# contbrd.net
KiCad netlist of a schematic drawn in EAGLE
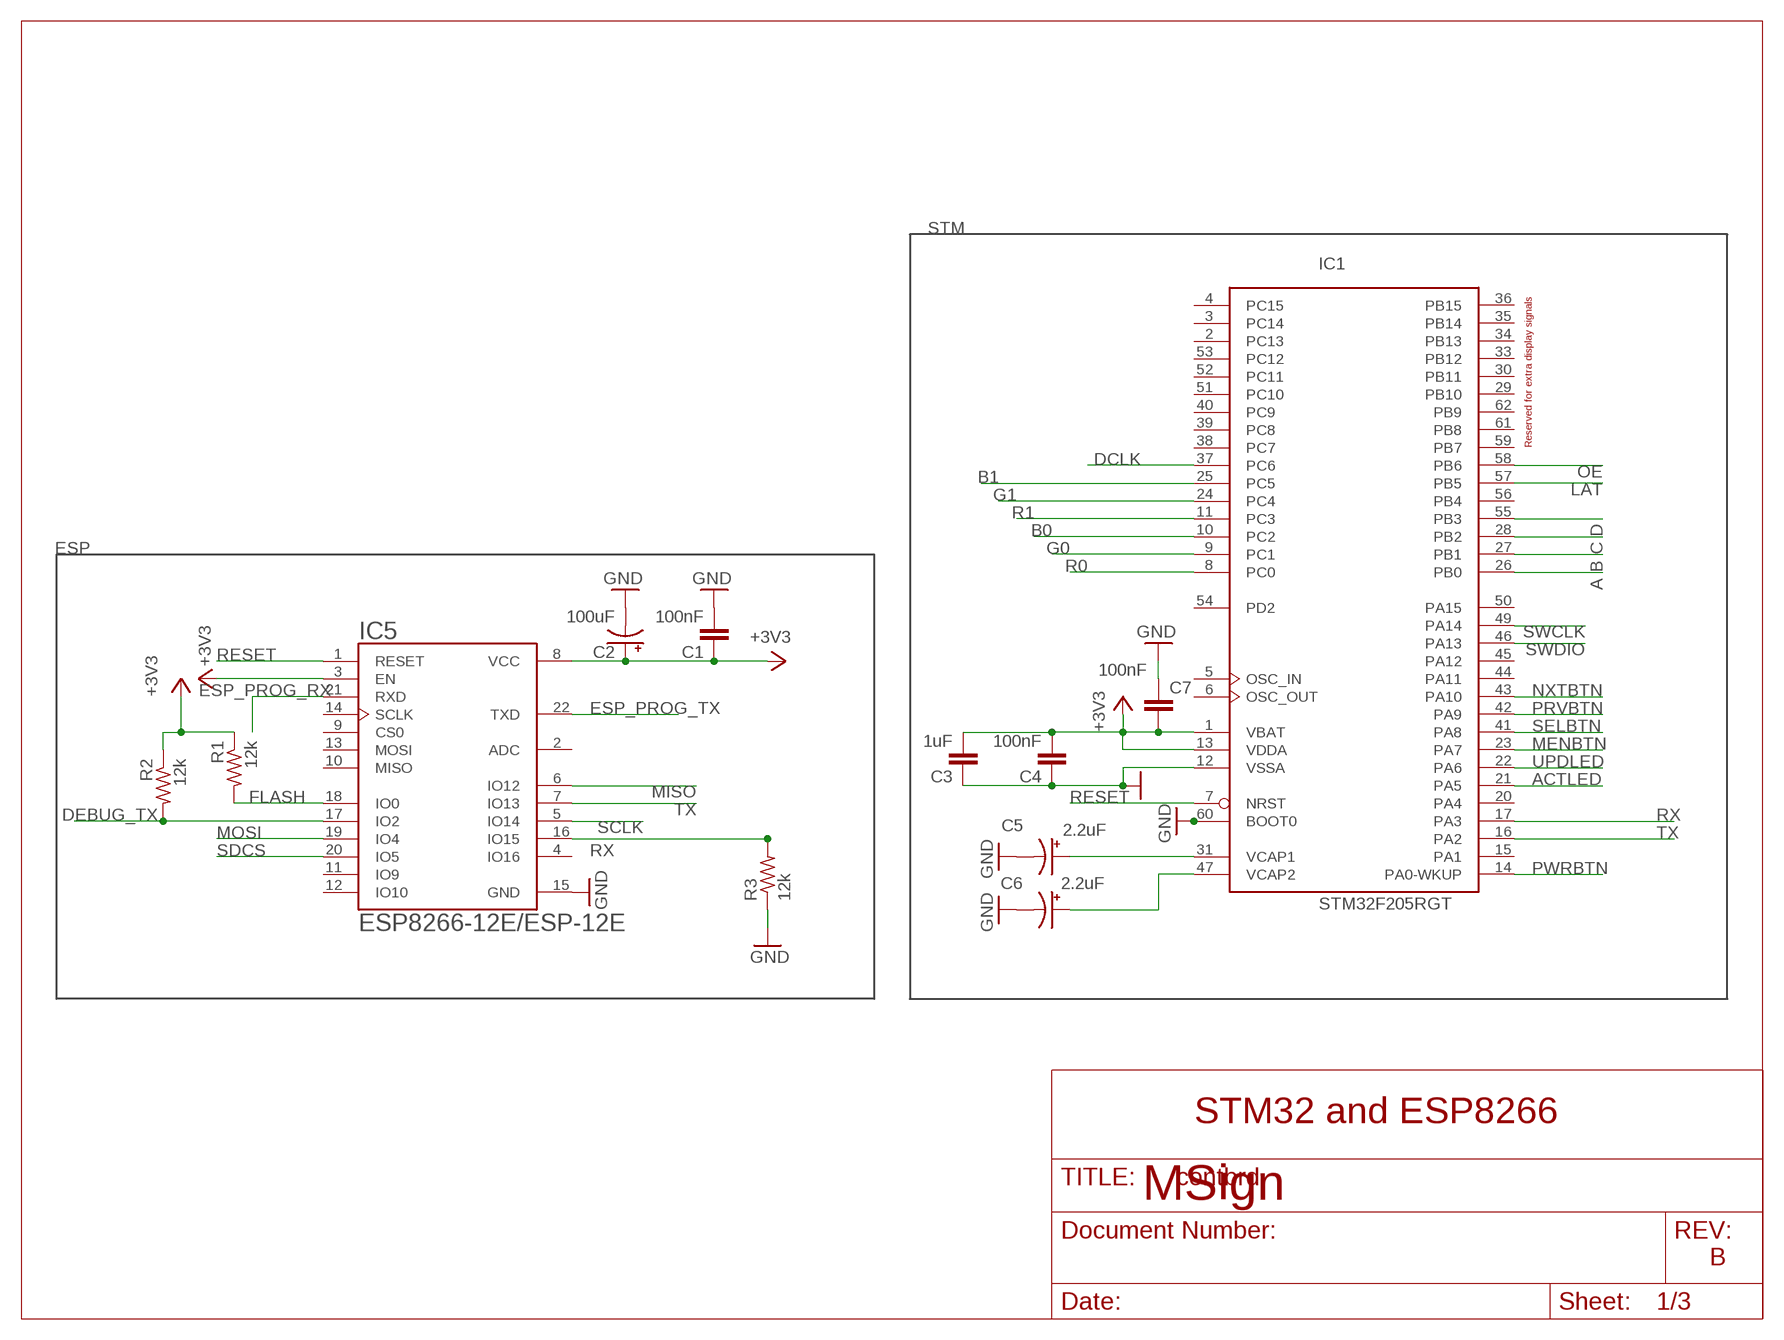
[diagram p0: schematic, sheet 1]
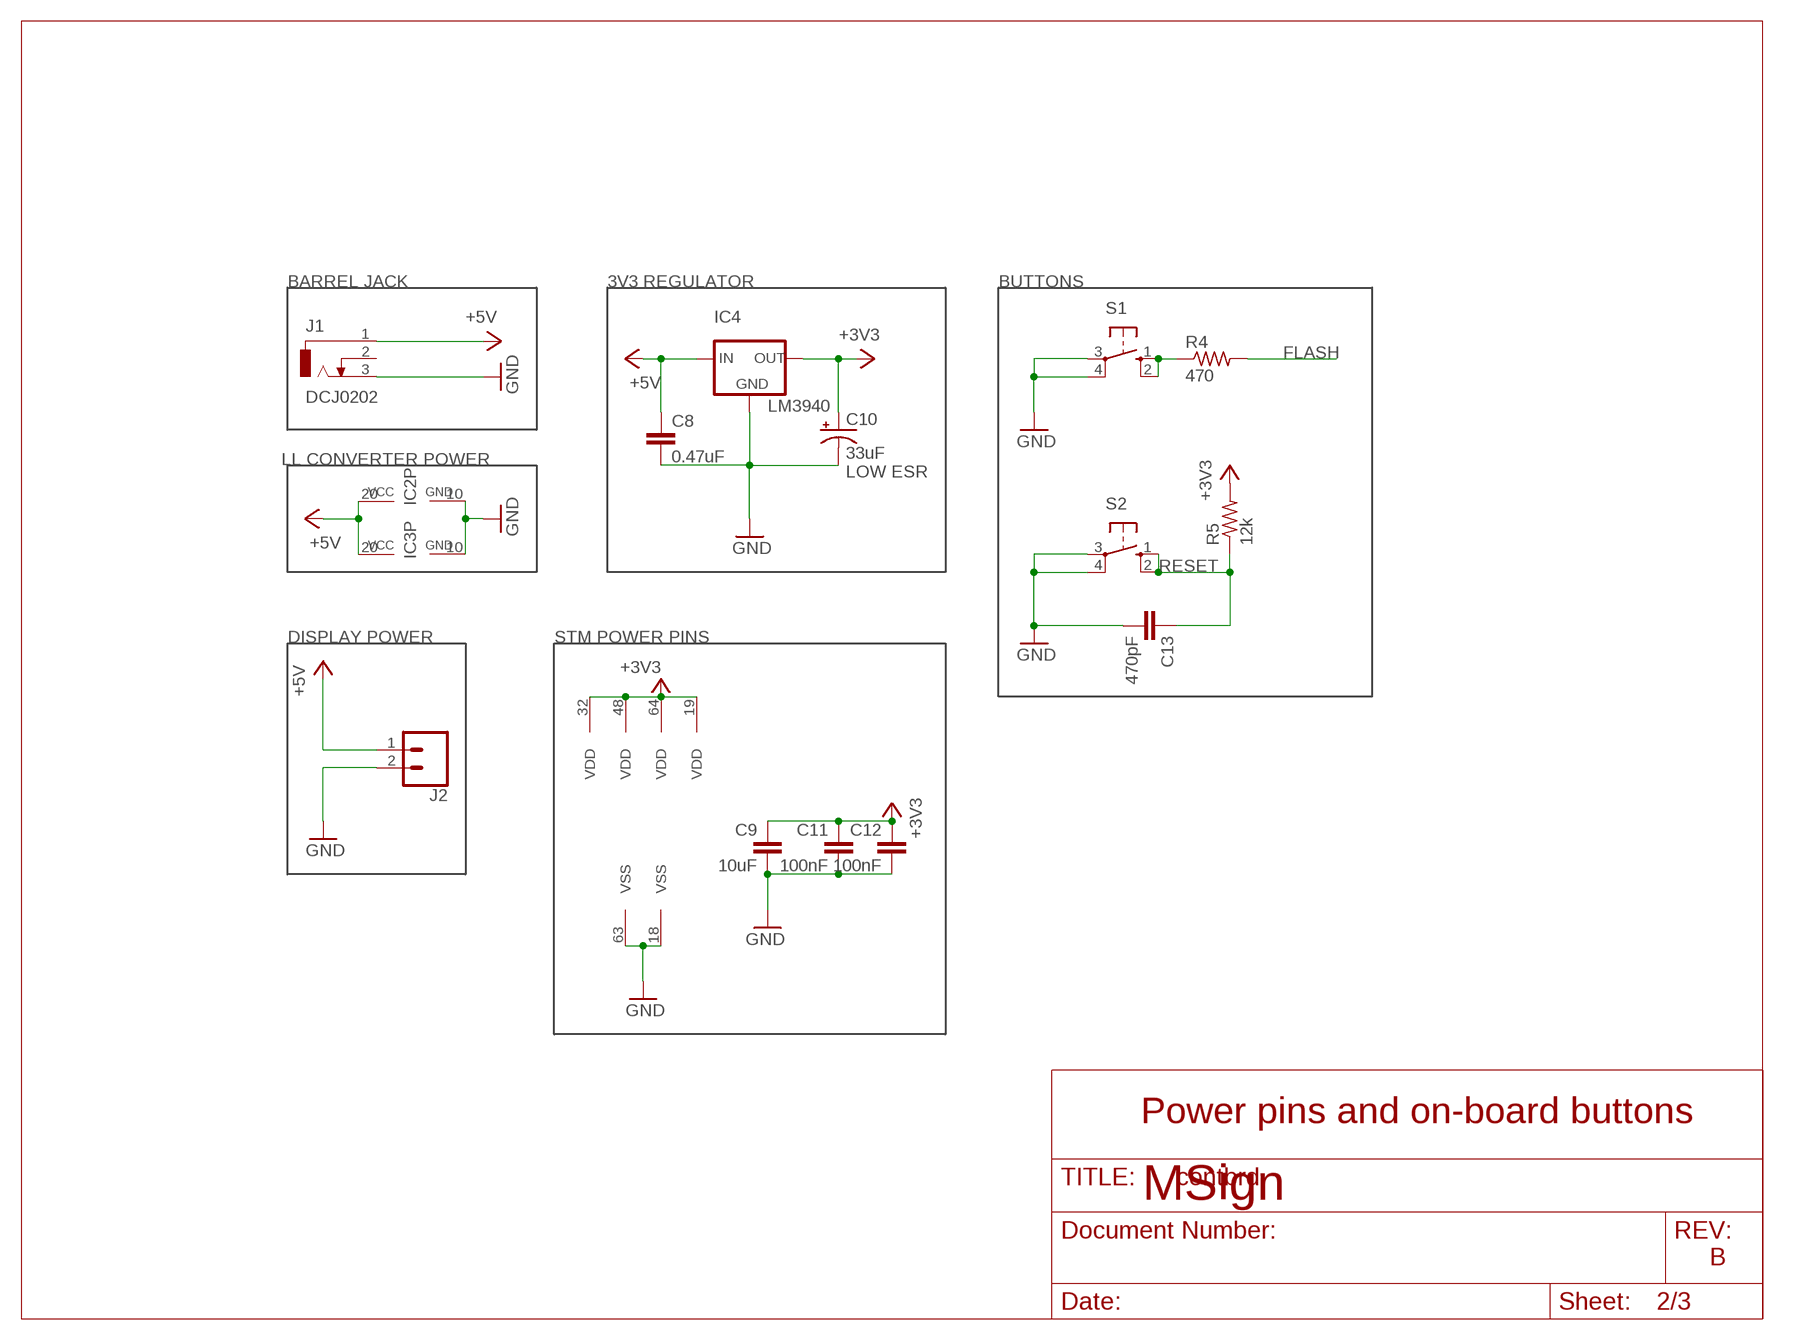
[diagram p1: schematic, sheet 2]
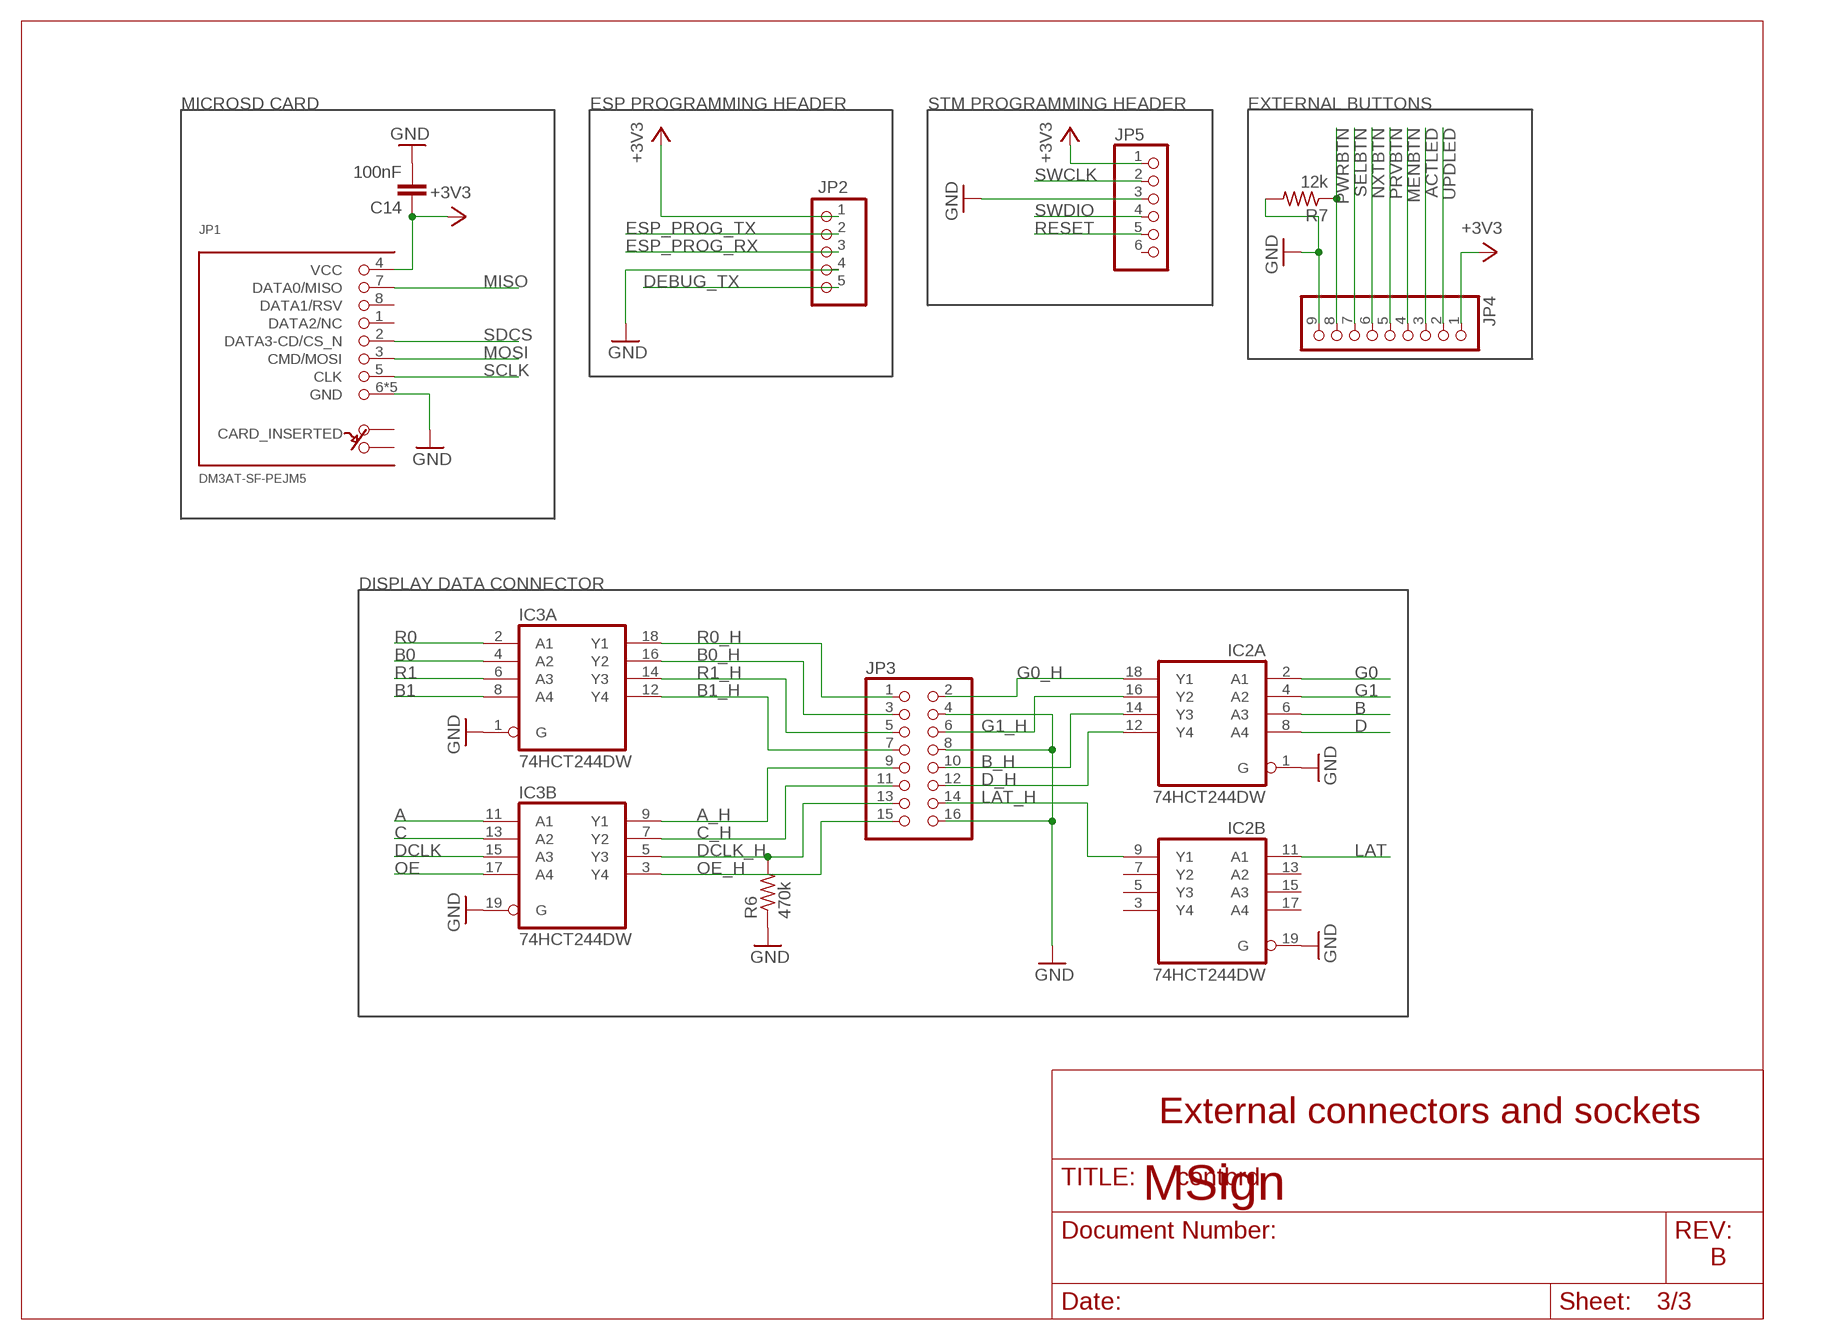
[diagram p2: schematic, sheet 3]

(export (version "E")
  (design (tool "Eeschema 10.0.6"))
  (components
    (comp (ref "C1")
      (value "100nF")
      (footprint "eagle-import:C025-025X050")
      (libsource (lib "eagle-import") (part "C-EU025-025X050"))
    )
    (comp (ref "C2")
      (value "100uF")
      (footprint "eagle-import:E2,5-6")
      (libsource (lib "eagle-import") (part "CPOL-USE2.5-6"))
    )
    (comp (ref "C3")
      (value "1uF")
      (footprint "eagle-import:C050-024X044")
      (libsource (lib "eagle-import") (part "C-EU050-024X044"))
    )
    (comp (ref "C4")
      (value "100nF")
      (footprint "eagle-import:C025-025X050")
      (libsource (lib "eagle-import") (part "C-EU025-025X050"))
    )
    (comp (ref "C5")
      (value "2.2uF")
      (footprint "eagle-import:E1,8-4")
      (libsource (lib "eagle-import") (part "CPOL-USE1.8-4"))
    )
    (comp (ref "C6")
      (value "2.2uF")
      (footprint "eagle-import:E1,8-4")
      (libsource (lib "eagle-import") (part "CPOL-USE1.8-4"))
    )
    (comp (ref "C7")
      (value "100nF")
      (footprint "eagle-import:C025-025X050")
      (libsource (lib "eagle-import") (part "C-EU025-025X050"))
    )
    (comp (ref "IC1")
      (value "STM32F205RGT")
      (footprint "eagle-import:LQFP64")
      (libsource (lib "eagle-import") (part "STM32F205RTG"))
    )
    (comp (ref "IC5")
      (value "ESP8266-12E/ESP-12E")
      (footprint "eagle-import:XCVR_ESP8266-12E_ESP-12E")
      (fields (field (name "MF") "AI-Thinker"))
      (libsource (lib "eagle-import") (part "ESP8266-12E/ESP-12E"))
    )
    (comp (ref "R1")
      (value "12k")
      (footprint "eagle-import:0204_7")
      (libsource (lib "eagle-import") (part "R-US_0204/7"))
    )
    (comp (ref "R2")
      (value "12k")
      (footprint "eagle-import:0204_7")
      (libsource (lib "eagle-import") (part "R-US_0204/7"))
    )
    (comp (ref "R3")
      (value "12k")
      (footprint "eagle-import:0204_7")
      (libsource (lib "eagle-import") (part "R-US_0204/7"))
    )
    (comp (ref "C8")
      (value "0.47uF")
      (footprint "eagle-import:C050-024X044")
      (libsource (lib "eagle-import") (part "C-EU050-024X044"))
    )
    (comp (ref "C9")
      (value "10uF")
      (footprint "eagle-import:C025-025X050")
      (libsource (lib "eagle-import") (part "C-EU025-025X050"))
    )
    (comp (ref "C10")
      (value "33uF")
      (footprint "eagle-import:E2-5")
      (libsource (lib "eagle-import") (part "CPOL-USE2-5"))
    )
    (comp (ref "C11")
      (value "100nF")
      (footprint "eagle-import:C025-025X050")
      (libsource (lib "eagle-import") (part "C-EU025-025X050"))
    )
    (comp (ref "C12")
      (value "100nF")
      (footprint "eagle-import:C025-025X050")
      (libsource (lib "eagle-import") (part "C-EU025-025X050"))
    )
    (comp (ref "C13")
      (value "470pF")
      (footprint "eagle-import:C025-025X050")
      (libsource (lib "eagle-import") (part "C-EU025-025X050"))
    )
    (comp (ref "IC2")
      (value "74HCT244DW")
      (footprint "eagle-import:SO20W")
      (libsource (lib "eagle-import") (part "74244DWHCT"))
    )
    (comp (ref "IC3")
      (value "74HCT244DW")
      (footprint "eagle-import:SO20W")
      (libsource (lib "eagle-import") (part "74244DWHCT"))
    )
    (comp (ref "IC4")
      (value "LM3940")
      (footprint "eagle-import:TO220")
      (fields (field (name "MF") "Texas Instruments"))
      (libsource (lib "eagle-import") (part "LM3940"))
    )
    (comp (ref "J1")
      (value "DCJ0202")
      (footprint "eagle-import:DCJ0202")
      (libsource (lib "eagle-import") (part "DCJ0202"))
    )
    (comp (ref "J2")
      (value "CONN_025MM")
      (footprint "eagle-import:SCREWTERMINAL-5MM-2")
      (libsource (lib "eagle-import") (part "CONN_025MM"))
    )
    (comp (ref "R4")
      (value "470")
      (footprint "eagle-import:0204_7")
      (libsource (lib "eagle-import") (part "R-US_0204/7"))
    )
    (comp (ref "R5")
      (value "12k")
      (footprint "eagle-import:0204_7")
      (libsource (lib "eagle-import") (part "R-US_0204/7"))
    )
    (comp (ref "S1")
      (value "10-XX")
      (footprint "eagle-import:B3F-10XX")
      (fields (field (name "MPN") "B3F-1000"))
      (libsource (lib "eagle-import") (part "10-XX"))
    )
    (comp (ref "S2")
      (value "10-XX")
      (footprint "eagle-import:B3F-10XX")
      (fields (field (name "MPN") "B3F-1000"))
      (libsource (lib "eagle-import") (part "10-XX"))
    )
    (comp (ref "C14")
      (value "100nF")
      (footprint "eagle-import:C025-025X050")
      (libsource (lib "eagle-import") (part "C-EU025-025X050"))
    )
    (comp (ref "JP1")
      (value "DM3AT-SF-PEJM5")
      (footprint "eagle-import:DM3AT-SF-PEJM5")
      (fields (field (name "MANUFACTURER") "Hirose Electric Co Ltd"))
      (libsource (lib "eagle-import") (part "DM3AT-SF-PEJM5"))
    )
    (comp (ref "JP2")
      (value "PINHD-1X5")
      (footprint "eagle-import:1X05")
      (libsource (lib "eagle-import") (part "PINHD-1X5"))
    )
    (comp (ref "JP3")
      (value "PINHD-2X8")
      (footprint "eagle-import:2X08")
      (libsource (lib "eagle-import") (part "PINHD-2X8"))
    )
    (comp (ref "JP4")
      (value "PINHD-1X9")
      (footprint "eagle-import:1X09")
      (libsource (lib "eagle-import") (part "PINHD-1X9"))
    )
    (comp (ref "JP5")
      (value "PINHD-1X6")
      (footprint "eagle-import:1X06")
      (libsource (lib "eagle-import") (part "PINHD-1X6"))
    )
    (comp (ref "R6")
      (value "470k")
      (footprint "eagle-import:0204_7")
      (libsource (lib "eagle-import") (part "R-US_0204/7"))
    )
    (comp (ref "R7")
      (value "12k")
      (footprint "eagle-import:0204_7")
      (libsource (lib "eagle-import") (part "R-US_0204/7"))
    )
  )
  (nets
    (net (code "1") (name "+3V3") (class "Default")
      (node (ref "C1") (pin "1") (pinfunction "1_1") (pintype "passive"))
      (node (ref "C10") (pin "+") (pinfunction "+_+") (pintype "passive"))
      (node (ref "C11") (pin "1") (pinfunction "1_1") (pintype "passive"))
      (node (ref "C12") (pin "1") (pinfunction "1_1") (pintype "passive"))
      (node (ref "C14") (pin "1") (pinfunction "1_1") (pintype "passive"))
      (node (ref "C2") (pin "+") (pinfunction "+_+") (pintype "passive"))
      (node (ref "C3") (pin "2") (pinfunction "2_2") (pintype "passive"))
      (node (ref "C4") (pin "2") (pinfunction "2_2") (pintype "passive"))
      (node (ref "C7") (pin "2") (pinfunction "2_2") (pintype "passive"))
      (node (ref "C9") (pin "1") (pinfunction "1_1") (pintype "passive"))
      (node (ref "IC1") (pin "1") (pinfunction "VBAT_1") (pintype "power_in"))
      (node (ref "IC1") (pin "13") (pinfunction "VDDA_13") (pintype "power_in"))
      (node (ref "IC1") (pin "19") (pinfunction "VDD_19") (pintype "power_in"))
      (node (ref "IC1") (pin "32") (pinfunction "VDD_32") (pintype "power_in"))
      (node (ref "IC1") (pin "48") (pinfunction "VDD_48") (pintype "power_in"))
      (node (ref "IC1") (pin "64") (pinfunction "VDD_64") (pintype "power_in"))
      (node (ref "IC4") (pin "3") (pinfunction "OUT_3") (pintype "output"))
      (node (ref "IC5") (pin "3") (pinfunction "EN_3") (pintype "input"))
      (node (ref "IC5") (pin "8") (pinfunction "VCC_8") (pintype "power_in"))
      (node (ref "JP1") (pin "4") (pinfunction "VCC_4") (pintype "bidirectional"))
      (node (ref "JP2") (pin "1") (pinfunction "1_1") (pintype "passive"))
      (node (ref "JP4") (pin "1") (pinfunction "1_1") (pintype "passive"))
      (node (ref "JP5") (pin "1") (pinfunction "1_1") (pintype "passive"))
      (node (ref "R1") (pin "1") (pinfunction "1_1") (pintype "passive"))
      (node (ref "R2") (pin "1") (pinfunction "1_1") (pintype "passive"))
      (node (ref "R5") (pin "2") (pinfunction "2_2") (pintype "passive"))
    )
    (net (code "2") (name "+5V") (class "Default")
      (node (ref "C8") (pin "1") (pinfunction "1_1") (pintype "passive"))
      (node (ref "IC2") (pin "20") (pinfunction "VCC_20") (pintype "power_in"))
      (node (ref "IC3") (pin "20") (pinfunction "VCC_20") (pintype "power_in"))
      (node (ref "IC4") (pin "1") (pinfunction "IN_1") (pintype "input"))
      (node (ref "J1") (pin "1") (pinfunction "1_1") (pintype "passive"))
      (node (ref "J2") (pin "1") (pinfunction "1_1") (pintype "passive"))
    )
    (net (code "3") (name "A") (class "Default")
      (node (ref "IC1") (pin "26") (pinfunction "PB0_26") (pintype "bidirectional"))
      (node (ref "IC3") (pin "11") (pinfunction "A1_11") (pintype "input"))
    )
    (net (code "4") (name "ACTLED") (class "Default")
      (node (ref "IC1") (pin "21") (pinfunction "PA5_21") (pintype "bidirectional"))
      (node (ref "JP4") (pin "3") (pinfunction "3_3") (pintype "passive"))
    )
    (net (code "5") (name "A_H") (class "Default")
      (node (ref "IC3") (pin "9") (pinfunction "Y1_9") (pintype "tri_state"))
      (node (ref "JP3") (pin "9") (pinfunction "9_9") (pintype "passive"))
    )
    (net (code "6") (name "B") (class "Default")
      (node (ref "IC1") (pin "27") (pinfunction "PB1_27") (pintype "bidirectional"))
      (node (ref "IC2") (pin "6") (pinfunction "A3_6") (pintype "input"))
    )
    (net (code "7") (name "B0") (class "Default")
      (node (ref "IC1") (pin "10") (pinfunction "PC2_10") (pintype "bidirectional"))
      (node (ref "IC3") (pin "4") (pinfunction "A2_4") (pintype "input"))
    )
    (net (code "8") (name "B0_H") (class "Default")
      (node (ref "IC3") (pin "16") (pinfunction "Y2_16") (pintype "tri_state"))
      (node (ref "JP3") (pin "3") (pinfunction "3_3") (pintype "passive"))
    )
    (net (code "9") (name "B1") (class "Default")
      (node (ref "IC1") (pin "25") (pinfunction "PC5_25") (pintype "bidirectional"))
      (node (ref "IC3") (pin "8") (pinfunction "A4_8") (pintype "input"))
    )
    (net (code "10") (name "B1_H") (class "Default")
      (node (ref "IC3") (pin "12") (pinfunction "Y4_12") (pintype "tri_state"))
      (node (ref "JP3") (pin "7") (pinfunction "7_7") (pintype "passive"))
    )
    (net (code "11") (name "B_H") (class "Default")
      (node (ref "IC2") (pin "14") (pinfunction "Y3_14") (pintype "tri_state"))
      (node (ref "JP3") (pin "10") (pinfunction "10_10") (pintype "passive"))
    )
    (net (code "12") (name "C") (class "Default")
      (node (ref "IC1") (pin "28") (pinfunction "PB2_28") (pintype "bidirectional"))
      (node (ref "IC3") (pin "13") (pinfunction "A2_13") (pintype "input"))
    )
    (net (code "13") (name "C_H") (class "Default")
      (node (ref "IC3") (pin "7") (pinfunction "Y2_7") (pintype "tri_state"))
      (node (ref "JP3") (pin "11") (pinfunction "11_11") (pintype "passive"))
    )
    (net (code "14") (name "D") (class "Default")
      (node (ref "IC1") (pin "55") (pinfunction "PB3_55") (pintype "bidirectional"))
      (node (ref "IC2") (pin "8") (pinfunction "A4_8") (pintype "input"))
    )
    (net (code "15") (name "DCLK") (class "Default")
      (node (ref "IC1") (pin "37") (pinfunction "PC6_37") (pintype "bidirectional"))
      (node (ref "IC3") (pin "15") (pinfunction "A3_15") (pintype "input"))
    )
    (net (code "16") (name "DCLK_H") (class "Default")
      (node (ref "IC3") (pin "5") (pinfunction "Y3_5") (pintype "tri_state"))
      (node (ref "JP3") (pin "13") (pinfunction "13_13") (pintype "passive"))
      (node (ref "R6") (pin "2") (pinfunction "2_2") (pintype "passive"))
    )
    (net (code "17") (name "DEBUG_TX") (class "Default")
      (node (ref "IC5") (pin "17") (pinfunction "IO2_17") (pintype "bidirectional"))
      (node (ref "JP2") (pin "5") (pinfunction "5_5") (pintype "passive"))
      (node (ref "R2") (pin "2") (pinfunction "2_2") (pintype "passive"))
    )
    (net (code "18") (name "D_H") (class "Default")
      (node (ref "IC2") (pin "12") (pinfunction "Y4_12") (pintype "tri_state"))
      (node (ref "JP3") (pin "12") (pinfunction "12_12") (pintype "passive"))
    )
    (net (code "19") (name "ESP_PROG_RX") (class "Default")
      (node (ref "IC5") (pin "21") (pinfunction "RXD_21") (pintype "input"))
      (node (ref "JP2") (pin "3") (pinfunction "3_3") (pintype "passive"))
    )
    (net (code "20") (name "ESP_PROG_TX") (class "Default")
      (node (ref "IC5") (pin "22") (pinfunction "TXD_22") (pintype "output"))
      (node (ref "JP2") (pin "2") (pinfunction "2_2") (pintype "passive"))
    )
    (net (code "21") (name "FLASH") (class "Default")
      (node (ref "IC5") (pin "18") (pinfunction "IO0_18") (pintype "bidirectional"))
      (node (ref "R1") (pin "2") (pinfunction "2_2") (pintype "passive"))
      (node (ref "R4") (pin "2") (pinfunction "2_2") (pintype "passive"))
    )
    (net (code "22") (name "G0") (class "Default")
      (node (ref "IC1") (pin "9") (pinfunction "PC1_9") (pintype "bidirectional"))
      (node (ref "IC2") (pin "2") (pinfunction "A1_2") (pintype "input"))
    )
    (net (code "23") (name "G0_H") (class "Default")
      (node (ref "IC2") (pin "18") (pinfunction "Y1_18") (pintype "tri_state"))
      (node (ref "JP3") (pin "2") (pinfunction "2_2") (pintype "passive"))
    )
    (net (code "24") (name "G1") (class "Default")
      (node (ref "IC1") (pin "24") (pinfunction "PC4_24") (pintype "bidirectional"))
      (node (ref "IC2") (pin "4") (pinfunction "A2_4") (pintype "input"))
    )
    (net (code "25") (name "G1_H") (class "Default")
      (node (ref "IC2") (pin "16") (pinfunction "Y2_16") (pintype "tri_state"))
      (node (ref "JP3") (pin "6") (pinfunction "6_6") (pintype "passive"))
    )
    (net (code "26") (name "GND") (class "Default")
      (node (ref "C1") (pin "2") (pinfunction "2_2") (pintype "passive"))
      (node (ref "C10") (pin "-") (pinfunction "-_-") (pintype "passive"))
      (node (ref "C11") (pin "2") (pinfunction "2_2") (pintype "passive"))
      (node (ref "C12") (pin "2") (pinfunction "2_2") (pintype "passive"))
      (node (ref "C13") (pin "2") (pinfunction "2_2") (pintype "passive"))
      (node (ref "C14") (pin "2") (pinfunction "2_2") (pintype "passive"))
      (node (ref "C2") (pin "-") (pinfunction "-_-") (pintype "passive"))
      (node (ref "C3") (pin "1") (pinfunction "1_1") (pintype "passive"))
      (node (ref "C4") (pin "1") (pinfunction "1_1") (pintype "passive"))
      (node (ref "C5") (pin "-") (pinfunction "-_-") (pintype "passive"))
      (node (ref "C6") (pin "-") (pinfunction "-_-") (pintype "passive"))
      (node (ref "C7") (pin "1") (pinfunction "1_1") (pintype "passive"))
      (node (ref "C8") (pin "2") (pinfunction "2_2") (pintype "passive"))
      (node (ref "C9") (pin "2") (pinfunction "2_2") (pintype "passive"))
      (node (ref "IC1") (pin "12") (pinfunction "VSSA_12") (pintype "power_in"))
      (node (ref "IC1") (pin "18") (pinfunction "VSS_18") (pintype "power_in"))
      (node (ref "IC1") (pin "60") (pinfunction "BOOT0_60") (pintype "input"))
      (node (ref "IC1") (pin "63") (pinfunction "VSS_63") (pintype "power_in"))
      (node (ref "IC2") (pin "1") (pinfunction "G_1") (pintype "input"))
      (node (ref "IC2") (pin "10") (pinfunction "GND_10") (pintype "power_in"))
      (node (ref "IC2") (pin "19") (pinfunction "G_19") (pintype "input"))
      (node (ref "IC3") (pin "1") (pinfunction "G_1") (pintype "input"))
      (node (ref "IC3") (pin "10") (pinfunction "GND_10") (pintype "power_in"))
      (node (ref "IC3") (pin "19") (pinfunction "G_19") (pintype "input"))
      (node (ref "IC4") (pin "2") (pinfunction "GND_2") (pintype "input"))
      (node (ref "IC5") (pin "15") (pinfunction "GND_15") (pintype "power_in"))
      (node (ref "J1") (pin "3") (pinfunction "3_3") (pintype "passive"))
      (node (ref "J2") (pin "2") (pinfunction "2_2") (pintype "passive"))
      (node (ref "JP1") (pin "6") (pinfunction "GND_6") (pintype "bidirectional"))
      (node (ref "JP1") (pin "MOUNT0") (pinfunction "GND_MOUNT0") (pintype "bidirectional"))
      (node (ref "JP1") (pin "MOUNT1") (pinfunction "GND_MOUNT1") (pintype "bidirectional"))
      (node (ref "JP1") (pin "MOUNT2") (pinfunction "GND_MOUNT2") (pintype "bidirectional"))
      (node (ref "JP1") (pin "MOUNT3") (pinfunction "GND_MOUNT3") (pintype "bidirectional"))
      (node (ref "JP2") (pin "4") (pinfunction "4_4") (pintype "passive"))
      (node (ref "JP3") (pin "16") (pinfunction "16_16") (pintype "passive"))
      (node (ref "JP3") (pin "4") (pinfunction "4_4") (pintype "passive"))
      (node (ref "JP3") (pin "8") (pinfunction "8_8") (pintype "passive"))
      (node (ref "JP4") (pin "9") (pinfunction "9_9") (pintype "passive"))
      (node (ref "JP5") (pin "3") (pinfunction "3_3") (pintype "passive"))
      (node (ref "R3") (pin "1") (pinfunction "1_1") (pintype "passive"))
      (node (ref "R6") (pin "1") (pinfunction "1_1") (pintype "passive"))
      (node (ref "R7") (pin "2") (pinfunction "2_2") (pintype "passive"))
      (node (ref "S1") (pin "3") (pinfunction "P_3") (pintype "passive"))
      (node (ref "S1") (pin "4") (pinfunction "P1_4") (pintype "passive"))
      (node (ref "S2") (pin "3") (pinfunction "P_3") (pintype "passive"))
      (node (ref "S2") (pin "4") (pinfunction "P1_4") (pintype "passive"))
    )
    (net (code "27") (name "LAT") (class "Default")
      (node (ref "IC1") (pin "57") (pinfunction "PB5_57") (pintype "bidirectional"))
      (node (ref "IC2") (pin "11") (pinfunction "A1_11") (pintype "input"))
    )
    (net (code "28") (name "LAT_H") (class "Default")
      (node (ref "IC2") (pin "9") (pinfunction "Y1_9") (pintype "tri_state"))
      (node (ref "JP3") (pin "14") (pinfunction "14_14") (pintype "passive"))
    )
    (net (code "29") (name "MENBTN") (class "Default")
      (node (ref "IC1") (pin "23") (pinfunction "PA7_23") (pintype "bidirectional"))
      (node (ref "JP4") (pin "4") (pinfunction "4_4") (pintype "passive"))
    )
    (net (code "30") (name "MISO") (class "Default")
      (node (ref "IC5") (pin "6") (pinfunction "IO12_6") (pintype "bidirectional"))
      (node (ref "JP1") (pin "7") (pinfunction "DATA0/MISO_7") (pintype "bidirectional"))
    )
    (net (code "31") (name "MOSI") (class "Default")
      (node (ref "IC5") (pin "19") (pinfunction "IO4_19") (pintype "bidirectional"))
      (node (ref "JP1") (pin "3") (pinfunction "CMD/MOSI_3") (pintype "bidirectional"))
    )
    (net (code "32") (name "NXTBTN") (class "Default")
      (node (ref "IC1") (pin "43") (pinfunction "PA10_43") (pintype "bidirectional"))
      (node (ref "JP4") (pin "6") (pinfunction "6_6") (pintype "passive"))
    )
    (net (code "33") (name "Net-(IC1A-VCAP1)") (class "Default")
      (node (ref "C5") (pin "+") (pinfunction "+_+") (pintype "passive"))
      (node (ref "IC1") (pin "31") (pinfunction "VCAP1_31") (pintype "power_in"))
    )
    (net (code "34") (name "Net-(IC1A-VCAP2)") (class "Default")
      (node (ref "C6") (pin "+") (pinfunction "+_+") (pintype "passive"))
      (node (ref "IC1") (pin "47") (pinfunction "VCAP2_47") (pintype "power_in"))
    )
    (net (code "35") (name "Net-(S1-S)") (class "Default")
      (node (ref "R4") (pin "1") (pinfunction "1_1") (pintype "passive"))
      (node (ref "S1") (pin "1") (pinfunction "S_1") (pintype "passive"))
      (node (ref "S1") (pin "2") (pinfunction "S1_2") (pintype "passive"))
    )
    (net (code "36") (name "OE") (class "Default")
      (node (ref "IC1") (pin "58") (pinfunction "PB6_58") (pintype "bidirectional"))
      (node (ref "IC3") (pin "17") (pinfunction "A4_17") (pintype "input"))
    )
    (net (code "37") (name "OE_H") (class "Default")
      (node (ref "IC3") (pin "3") (pinfunction "Y4_3") (pintype "tri_state"))
      (node (ref "JP3") (pin "15") (pinfunction "15_15") (pintype "passive"))
    )
    (net (code "38") (name "PRVBTN") (class "Default")
      (node (ref "IC1") (pin "42") (pinfunction "PA9_42") (pintype "bidirectional"))
      (node (ref "JP4") (pin "5") (pinfunction "5_5") (pintype "passive"))
    )
    (net (code "39") (name "PWRBTN") (class "Default")
      (node (ref "IC1") (pin "14") (pinfunction "PA0-WKUP_14") (pintype "bidirectional"))
      (node (ref "JP4") (pin "8") (pinfunction "8_8") (pintype "passive"))
      (node (ref "R7") (pin "1") (pinfunction "1_1") (pintype "passive"))
    )
    (net (code "40") (name "R0") (class "Default")
      (node (ref "IC1") (pin "8") (pinfunction "PC0_8") (pintype "bidirectional"))
      (node (ref "IC3") (pin "2") (pinfunction "A1_2") (pintype "input"))
    )
    (net (code "41") (name "R0_H") (class "Default")
      (node (ref "IC3") (pin "18") (pinfunction "Y1_18") (pintype "tri_state"))
      (node (ref "JP3") (pin "1") (pinfunction "1_1") (pintype "passive"))
    )
    (net (code "42") (name "R1") (class "Default")
      (node (ref "IC1") (pin "11") (pinfunction "PC3_11") (pintype "bidirectional"))
      (node (ref "IC3") (pin "6") (pinfunction "A3_6") (pintype "input"))
    )
    (net (code "43") (name "R1_H") (class "Default")
      (node (ref "IC3") (pin "14") (pinfunction "Y3_14") (pintype "tri_state"))
      (node (ref "JP3") (pin "5") (pinfunction "5_5") (pintype "passive"))
    )
    (net (code "44") (name "RESET") (class "Default")
      (node (ref "C13") (pin "1") (pinfunction "1_1") (pintype "passive"))
      (node (ref "IC1") (pin "7") (pinfunction "NRST_7") (pintype "bidirectional"))
      (node (ref "IC5") (pin "1") (pinfunction "RESET_1") (pintype "input"))
      (node (ref "JP5") (pin "5") (pinfunction "5_5") (pintype "passive"))
      (node (ref "R5") (pin "1") (pinfunction "1_1") (pintype "passive"))
      (node (ref "S2") (pin "1") (pinfunction "S_1") (pintype "passive"))
      (node (ref "S2") (pin "2") (pinfunction "S1_2") (pintype "passive"))
    )
    (net (code "45") (name "RX") (class "Default")
      (node (ref "IC1") (pin "17") (pinfunction "PA3_17") (pintype "bidirectional"))
      (node (ref "IC5") (pin "16") (pinfunction "IO15_16") (pintype "bidirectional"))
      (node (ref "R3") (pin "2") (pinfunction "2_2") (pintype "passive"))
    )
    (net (code "46") (name "SCLK") (class "Default")
      (node (ref "IC5") (pin "5") (pinfunction "IO14_5") (pintype "bidirectional"))
      (node (ref "JP1") (pin "5") (pinfunction "CLK_5") (pintype "bidirectional"))
    )
    (net (code "47") (name "SDCS") (class "Default")
      (node (ref "IC5") (pin "20") (pinfunction "IO5_20") (pintype "bidirectional"))
      (node (ref "JP1") (pin "2") (pinfunction "DATA3-CD/CS_N_2") (pintype "bidirectional"))
    )
    (net (code "48") (name "SELBTN") (class "Default")
      (node (ref "IC1") (pin "41") (pinfunction "PA8_41") (pintype "bidirectional"))
      (node (ref "JP4") (pin "7") (pinfunction "7_7") (pintype "passive"))
    )
    (net (code "49") (name "SWCLK") (class "Default")
      (node (ref "IC1") (pin "49") (pinfunction "PA14_49") (pintype "bidirectional"))
      (node (ref "JP5") (pin "2") (pinfunction "2_2") (pintype "passive"))
    )
    (net (code "50") (name "SWDIO") (class "Default")
      (node (ref "IC1") (pin "46") (pinfunction "PA13_46") (pintype "bidirectional"))
      (node (ref "JP5") (pin "4") (pinfunction "4_4") (pintype "passive"))
    )
    (net (code "51") (name "TX") (class "Default")
      (node (ref "IC1") (pin "16") (pinfunction "PA2_16") (pintype "bidirectional"))
      (node (ref "IC5") (pin "7") (pinfunction "IO13_7") (pintype "bidirectional"))
    )
    (net (code "52") (name "UPDLED") (class "Default")
      (node (ref "IC1") (pin "22") (pinfunction "PA6_22") (pintype "bidirectional"))
      (node (ref "JP4") (pin "2") (pinfunction "2_2") (pintype "passive"))
    )
    (net (code "53") (name "unconnected-(IC1A-OSC_IN-Pad5)") (class "Default")
      (node (ref "IC1") (pin "5") (pinfunction "OSC_IN_5") (pintype "bidirectional"))
    )
    (net (code "54") (name "unconnected-(IC1A-OSC_OUT-Pad6)") (class "Default")
      (node (ref "IC1") (pin "6") (pinfunction "OSC_OUT_6") (pintype "bidirectional"))
    )
    (net (code "55") (name "unconnected-(IC1A-PA1-Pad15)") (class "Default")
      (node (ref "IC1") (pin "15") (pinfunction "PA1_15") (pintype "bidirectional"))
    )
    (net (code "56") (name "unconnected-(IC1A-PA4-Pad20)") (class "Default")
      (node (ref "IC1") (pin "20") (pinfunction "PA4_20") (pintype "bidirectional"))
    )
    (net (code "57") (name "unconnected-(IC1A-PA11-Pad44)") (class "Default")
      (node (ref "IC1") (pin "44") (pinfunction "PA11_44") (pintype "bidirectional"))
    )
    (net (code "58") (name "unconnected-(IC1A-PA12-Pad45)") (class "Default")
      (node (ref "IC1") (pin "45") (pinfunction "PA12_45") (pintype "bidirectional"))
    )
    (net (code "59") (name "unconnected-(IC1A-PA15-Pad50)") (class "Default")
      (node (ref "IC1") (pin "50") (pinfunction "PA15_50") (pintype "bidirectional"))
    )
    (net (code "60") (name "unconnected-(IC1A-PB4-Pad56)") (class "Default")
      (node (ref "IC1") (pin "56") (pinfunction "PB4_56") (pintype "bidirectional"))
    )
    (net (code "61") (name "unconnected-(IC1A-PB7-Pad59)") (class "Default")
      (node (ref "IC1") (pin "59") (pinfunction "PB7_59") (pintype "bidirectional"))
    )
    (net (code "62") (name "unconnected-(IC1A-PB8-Pad61)") (class "Default")
      (node (ref "IC1") (pin "61") (pinfunction "PB8_61") (pintype "bidirectional"))
    )
    (net (code "63") (name "unconnected-(IC1A-PB9-Pad62)") (class "Default")
      (node (ref "IC1") (pin "62") (pinfunction "PB9_62") (pintype "bidirectional"))
    )
    (net (code "64") (name "unconnected-(IC1A-PB10-Pad29)") (class "Default")
      (node (ref "IC1") (pin "29") (pinfunction "PB10_29") (pintype "bidirectional"))
    )
    (net (code "65") (name "unconnected-(IC1A-PB11-Pad30)") (class "Default")
      (node (ref "IC1") (pin "30") (pinfunction "PB11_30") (pintype "bidirectional"))
    )
    (net (code "66") (name "unconnected-(IC1A-PB12-Pad33)") (class "Default")
      (node (ref "IC1") (pin "33") (pinfunction "PB12_33") (pintype "bidirectional"))
    )
    (net (code "67") (name "unconnected-(IC1A-PB13-Pad34)") (class "Default")
      (node (ref "IC1") (pin "34") (pinfunction "PB13_34") (pintype "bidirectional"))
    )
    (net (code "68") (name "unconnected-(IC1A-PB14-Pad35)") (class "Default")
      (node (ref "IC1") (pin "35") (pinfunction "PB14_35") (pintype "bidirectional"))
    )
    (net (code "69") (name "unconnected-(IC1A-PB15-Pad36)") (class "Default")
      (node (ref "IC1") (pin "36") (pinfunction "PB15_36") (pintype "bidirectional"))
    )
    (net (code "70") (name "unconnected-(IC1A-PC7-Pad38)") (class "Default")
      (node (ref "IC1") (pin "38") (pinfunction "PC7_38") (pintype "bidirectional"))
    )
    (net (code "71") (name "unconnected-(IC1A-PC8-Pad39)") (class "Default")
      (node (ref "IC1") (pin "39") (pinfunction "PC8_39") (pintype "bidirectional"))
    )
    (net (code "72") (name "unconnected-(IC1A-PC9-Pad40)") (class "Default")
      (node (ref "IC1") (pin "40") (pinfunction "PC9_40") (pintype "bidirectional"))
    )
    (net (code "73") (name "unconnected-(IC1A-PC10-Pad51)") (class "Default")
      (node (ref "IC1") (pin "51") (pinfunction "PC10_51") (pintype "bidirectional"))
    )
    (net (code "74") (name "unconnected-(IC1A-PC11-Pad52)") (class "Default")
      (node (ref "IC1") (pin "52") (pinfunction "PC11_52") (pintype "bidirectional"))
    )
    (net (code "75") (name "unconnected-(IC1A-PC12-Pad53)") (class "Default")
      (node (ref "IC1") (pin "53") (pinfunction "PC12_53") (pintype "bidirectional"))
    )
    (net (code "76") (name "unconnected-(IC1A-PC13-Pad2)") (class "Default")
      (node (ref "IC1") (pin "2") (pinfunction "PC13_2") (pintype "bidirectional"))
    )
    (net (code "77") (name "unconnected-(IC1A-PC14-Pad3)") (class "Default")
      (node (ref "IC1") (pin "3") (pinfunction "PC14_3") (pintype "bidirectional"))
    )
    (net (code "78") (name "unconnected-(IC1A-PC15-Pad4)") (class "Default")
      (node (ref "IC1") (pin "4") (pinfunction "PC15_4") (pintype "bidirectional"))
    )
    (net (code "79") (name "unconnected-(IC1A-PD2-Pad54)") (class "Default")
      (node (ref "IC1") (pin "54") (pinfunction "PD2_54") (pintype "bidirectional"))
    )
    (net (code "80") (name "unconnected-(IC2B-A2-Pad13)") (class "Default")
      (node (ref "IC2") (pin "13") (pinfunction "A2_13") (pintype "input"))
    )
    (net (code "81") (name "unconnected-(IC2B-A3-Pad15)") (class "Default")
      (node (ref "IC2") (pin "15") (pinfunction "A3_15") (pintype "input"))
    )
    (net (code "82") (name "unconnected-(IC2B-A4-Pad17)") (class "Default")
      (node (ref "IC2") (pin "17") (pinfunction "A4_17") (pintype "input"))
    )
    (net (code "83") (name "unconnected-(IC2B-Y2-Pad7)") (class "Default")
      (node (ref "IC2") (pin "7") (pinfunction "Y2_7") (pintype "tri_state"))
    )
    (net (code "84") (name "unconnected-(IC2B-Y3-Pad5)") (class "Default")
      (node (ref "IC2") (pin "5") (pinfunction "Y3_5") (pintype "tri_state"))
    )
    (net (code "85") (name "unconnected-(IC2B-Y4-Pad3)") (class "Default")
      (node (ref "IC2") (pin "3") (pinfunction "Y4_3") (pintype "tri_state"))
    )
    (net (code "86") (name "unconnected-(IC5-ADC-Pad2)") (class "Default")
      (node (ref "IC5") (pin "2") (pinfunction "ADC_2") (pintype "passive"))
    )
    (net (code "87") (name "unconnected-(IC5-CS0-Pad9)") (class "Default")
      (node (ref "IC5") (pin "9") (pinfunction "CS0_9") (pintype "input"))
    )
    (net (code "88") (name "unconnected-(IC5-IO9-Pad11)") (class "Default")
      (node (ref "IC5") (pin "11") (pinfunction "IO9_11") (pintype "bidirectional"))
    )
    (net (code "89") (name "unconnected-(IC5-IO10-Pad12)") (class "Default")
      (node (ref "IC5") (pin "12") (pinfunction "IO10_12") (pintype "bidirectional"))
    )
    (net (code "90") (name "unconnected-(IC5-IO16-Pad4)") (class "Default")
      (node (ref "IC5") (pin "4") (pinfunction "IO16_4") (pintype "bidirectional"))
    )
    (net (code "91") (name "unconnected-(IC5-MISO-Pad10)") (class "Default")
      (node (ref "IC5") (pin "10") (pinfunction "MISO_10") (pintype "bidirectional"))
    )
    (net (code "92") (name "unconnected-(IC5-MOSI-Pad13)") (class "Default")
      (node (ref "IC5") (pin "13") (pinfunction "MOSI_13") (pintype "bidirectional"))
    )
    (net (code "93") (name "unconnected-(IC5-SCLK-Pad14)") (class "Default")
      (node (ref "IC5") (pin "14") (pinfunction "SCLK_14") (pintype "input"))
    )
    (net (code "94") (name "unconnected-(J1-Pad2)") (class "Default")
      (node (ref "J1") (pin "2") (pinfunction "2_2") (pintype "passive"))
    )
    (net (code "95") (name "unconnected-(JP1-DATA1{slash}RSV-Pad8)") (class "Default")
      (node (ref "JP1") (pin "8") (pinfunction "DATA1/RSV_8") (pintype "bidirectional"))
    )
    (net (code "96") (name "unconnected-(JP1-DATA2{slash}NC-Pad1)") (class "Default")
      (node (ref "JP1") (pin "1") (pinfunction "DATA2/NC_1") (pintype "bidirectional"))
    )
    (net (code "97") (name "unconnected-(JP1-PadA)") (class "Default")
      (node (ref "JP1") (pin "A") (pinfunction "A_A") (pintype "bidirectional"))
    )
    (net (code "98") (name "unconnected-(JP1-PadB)") (class "Default")
      (node (ref "JP1") (pin "B") (pinfunction "B_B") (pintype "bidirectional"))
    )
    (net (code "99") (name "unconnected-(JP5-Pad6)") (class "Default")
      (node (ref "JP5") (pin "6") (pinfunction "6_6") (pintype "passive"))
    )
  )
)
